# MCU.net
KiCad netlist of a schematic drawn in Altium Designer
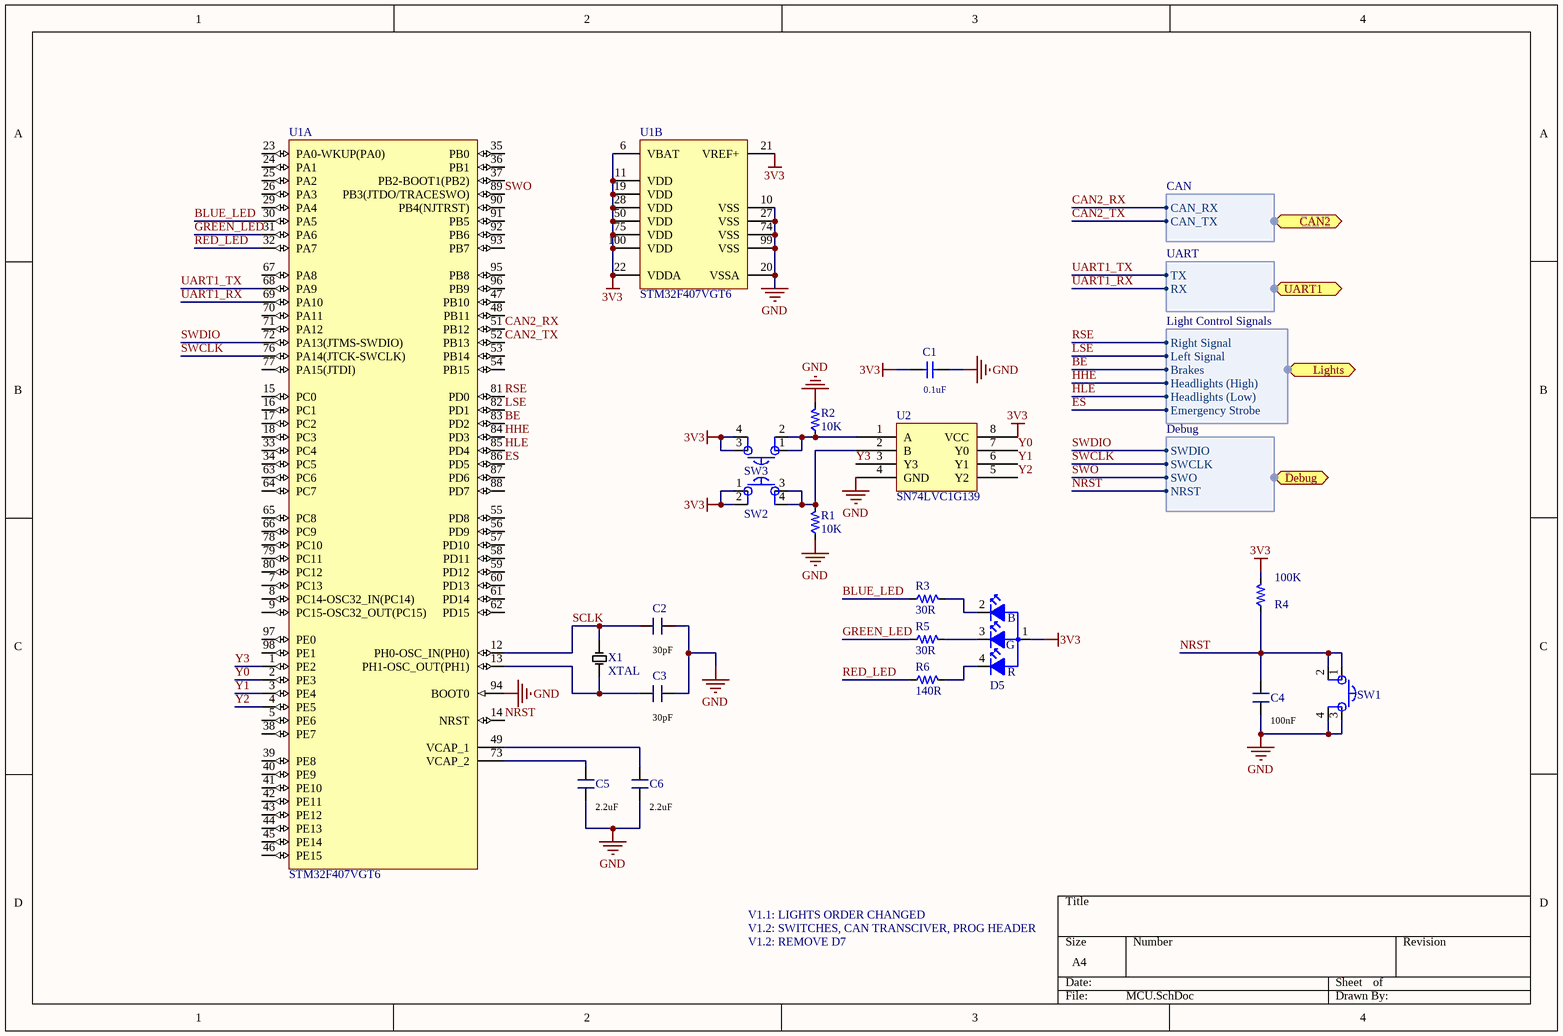
[diagram p0: MCU.SchDoc]

(export (version "E")
  (design (tool "Eeschema 10.0.6"))
  (components
    (comp (ref "C1")
      (value "SCH_GENERIC_CAPACITOR_0603")
      (footprint "PCB_GENERIC_SMD_0603")
      (description "Generic SMD capacitor 0603")
      (fields
        (field (name "TOLERANCE") "*%")
        (field (name "CAPACITANCE") "0.1uF")
        (field (name "VOLTAGE") "*V")
      )
      (libsource (lib "Generic 0603 Capacitor") (part "SCH_GENERIC_CAPACITOR_0603"))
    )
    (comp (ref "C2")
      (value "SCH_GENERIC_CAPACITOR_0603")
      (footprint "PCB_GENERIC_SMD_0603")
      (description "Generic SMD capacitor 0603")
      (fields (field (name "TOLERANCE") "*%") (field (name "CAPACITANCE") "30pF"))
      (libsource (lib "Capacitors") (part "SCH_GENERIC_CAPACITOR_0603"))
    )
    (comp (ref "C3")
      (value "SCH_GENERIC_CAPACITOR_0603")
      (footprint "PCB_GENERIC_SMD_0603")
      (description "Generic SMD capacitor 0603")
      (fields (field (name "TOLERANCE") "*%") (field (name "CAPACITANCE") "30pF"))
      (libsource (lib "Capacitors") (part "SCH_GENERIC_CAPACITOR_0603"))
    )
    (comp (ref "C4")
      (value "SCH_GENERIC_CAPACITOR_0603")
      (footprint "PCB_GENERIC_SMD_0603")
      (description "Generic SMD capacitor 0603")
      (fields (field (name "TOLERANCE") "*%") (field (name "CAPACITANCE") "100nF"))
      (libsource (lib "Capacitors") (part "SCH_GENERIC_CAPACITOR_0603"))
    )
    (comp (ref "C5")
      (value "SCH_GENERIC_CAPACITOR_0603")
      (footprint "PCB_GENERIC_SMD_0603")
      (description "Generic SMD capacitor 0603")
      (fields (field (name "TOLERANCE") "*%") (field (name "CAPACITANCE") "2.2uF"))
      (libsource (lib "Capacitors") (part "SCH_GENERIC_CAPACITOR_0603"))
    )
    (comp (ref "C6")
      (value "SCH_GENERIC_CAPACITOR_0603")
      (footprint "PCB_GENERIC_SMD_0603")
      (description "Generic SMD capacitor 0603")
      (fields (field (name "TOLERANCE") "*%") (field (name "CAPACITANCE") "2.2uF"))
      (libsource (lib "Capacitors") (part "SCH_GENERIC_CAPACITOR_0603"))
    )
    (comp (ref "D5")
      (value "D0S4-000CR-00")
      (footprint "CLMVB-FKA")
      (description "LED 4SMD RGB 2Vf 3Vf 3Vf 20mA 10mA 10mA")
      (libsource (lib "LED-4SMD") (part "D0S4-000CR-00"))
    )
    (comp (ref "R1")
      (value "SCH_GENERIC_RESISTOR_0603")
      (footprint "PCB_GENERIC_SMD_0603")
      (description "Generic SMD resistor 0603")
      (fields (field (name "RESISTANCE") "10K"))
      (libsource (lib "Generic 0603 Resistor") (part "SCH_GENERIC_RESISTOR_0603"))
    )
    (comp (ref "R2")
      (value "SCH_GENERIC_RESISTOR_0603")
      (footprint "PCB_GENERIC_SMD_0603")
      (description "Generic SMD resistor 0603")
      (fields (field (name "RESISTANCE") "10K"))
      (libsource (lib "Generic 0603 Resistor") (part "SCH_GENERIC_RESISTOR_0603"))
    )
    (comp (ref "R3")
      (value "SCH_GENERIC_RESISTOR_0603")
      (footprint "PCB_GENERIC_SMD_0603")
      (description "Generic SMD resistor 0603")
      (fields (field (name "RESISTANCE") "30R"))
      (libsource (lib "SCH_GENERIC_RESISTOR_0603") (part "SCH_GENERIC_RESISTOR_0603"))
    )
    (comp (ref "R4")
      (value "SCH_GENERIC_RESISTOR_0603")
      (footprint "PCB_GENERIC_SMD_0603")
      (description "Generic SMD resistor 0603")
      (fields (field (name "RESISTANCE") "100K"))
      (libsource (lib "Resistors") (part "SCH_GENERIC_RESISTOR_0603"))
    )
    (comp (ref "R5")
      (value "SCH_GENERIC_RESISTOR_0603")
      (footprint "PCB_GENERIC_SMD_0603")
      (description "Generic SMD resistor 0603")
      (fields (field (name "RESISTANCE") "30R"))
      (libsource (lib "SCH_GENERIC_RESISTOR_0603") (part "SCH_GENERIC_RESISTOR_0603"))
    )
    (comp (ref "R6")
      (value "SCH_GENERIC_RESISTOR_0603")
      (footprint "PCB_GENERIC_SMD_0603")
      (description "Generic SMD resistor 0603")
      (fields (field (name "RESISTANCE") "140R"))
      (libsource (lib "SCH_GENERIC_RESISTOR_0603") (part "SCH_GENERIC_RESISTOR_0603"))
    )
    (comp (ref "SW1")
      (value "Tactile Switch")
      (footprint "C&K 4 pin Tactile Switch")
      (libsource (lib "C&K 4 Pin Tactile Switch") (part "C&K Tactile Switch"))
    )
    (comp (ref "SW2")
      (value "Tactile Switch")
      (footprint "C&K 4 pin Tactile Switch")
      (libsource (lib "") (part "C&K Tactile Switch_1"))
    )
    (comp (ref "SW3")
      (value "Tactile Switch")
      (footprint "C&K 4 pin Tactile Switch")
      (libsource (lib "") (part "C&K Tactile Switch_1"))
    )
    (comp (ref "U1")
      (value "STM32F407VGT6")
      (footprint "STM-LQFP100_M")
      (fields (field (name "MANUFACTURER") "STMicroelectronics"))
      (libsource (lib "STMicroelectronics STM32 F4") (part "STM32F407VGT6"))
    )
    (comp (ref "U2")
      (value "SN74LVC1G139")
      (footprint "demux_24")
      (libsource (lib "demux") (part "demux_24"))
    )
    (comp (ref "X1") (value "XTAL") (footprint "CRYSTAL_8MHZ") (libsource (lib "Crystal") (part "Crystal")))
  )
  (nets
    (net (code "7") (name "/BE") (class "Default")
      (node (ref "U1") (pin "83") (pinfunction "PD2_83") (pintype "bidirectional"))
    )
    (net (code "8") (name "/BLUE_LED") (class "Default")
      (node (ref "R3") (pin "1") (pinfunction "1_1") (pintype "passive"))
      (node (ref "U1") (pin "30") (pinfunction "PA5_30") (pintype "bidirectional"))
    )
    (net (code "9") (name "/CAN2_RX") (class "Default")
      (node (ref "U1") (pin "51") (pinfunction "PB12_51") (pintype "bidirectional"))
    )
    (net (code "10") (name "/CAN2_TX") (class "Default")
      (node (ref "U1") (pin "52") (pinfunction "PB13_52") (pintype "bidirectional"))
    )
    (net (code "11") (name "/ES") (class "Default")
      (node (ref "U1") (pin "86") (pinfunction "PD5_86") (pintype "bidirectional"))
    )
    (net (code "12") (name "/GREEN_LED") (class "Default")
      (node (ref "R5") (pin "1") (pinfunction "1_1") (pintype "passive"))
      (node (ref "U1") (pin "31") (pinfunction "PA6_31") (pintype "bidirectional"))
    )
    (net (code "13") (name "/HHE") (class "Default")
      (node (ref "U1") (pin "84") (pinfunction "PD3_84") (pintype "bidirectional"))
    )
    (net (code "14") (name "/HLE") (class "Default")
      (node (ref "U1") (pin "85") (pinfunction "PD4_85") (pintype "bidirectional"))
    )
    (net (code "15") (name "/LSE") (class "Default")
      (node (ref "U1") (pin "82") (pinfunction "PD1_82") (pintype "bidirectional"))
    )
    (net (code "16") (name "/NRST") (class "Default")
      (node (ref "C4") (pin "1") (pinfunction "1_1") (pintype "passive"))
      (node (ref "R4") (pin "1") (pinfunction "1_1") (pintype "passive"))
      (node (ref "SW1") (pin "1") (pinfunction "1_1") (pintype "passive"))
      (node (ref "SW1") (pin "2") (pinfunction "2_2") (pintype "passive"))
      (node (ref "U1") (pin "14") (pinfunction "NRST_14") (pintype "bidirectional"))
    )
    (net (code "17") (name "/RED_LED") (class "Default")
      (node (ref "R6") (pin "1") (pinfunction "1_1") (pintype "passive"))
      (node (ref "U1") (pin "32") (pinfunction "PA7_32") (pintype "bidirectional"))
    )
    (net (code "18") (name "/RSE") (class "Default")
      (node (ref "U1") (pin "81") (pinfunction "PD0_81") (pintype "bidirectional"))
    )
    (net (code "19") (name "/SCLK") (class "Default")
      (node (ref "C2") (pin "2") (pinfunction "2_2") (pintype "passive"))
      (node (ref "U1") (pin "12") (pinfunction "PH0-OSC_IN(PH0)_12") (pintype "bidirectional"))
      (node (ref "X1") (pin "1") (pintype "passive"))
    )
    (net (code "20") (name "/SWCLK") (class "Default")
      (node (ref "U1") (pin "76") (pinfunction "PA14(JTCK-SWCLK)_76") (pintype "bidirectional"))
    )
    (net (code "21") (name "/SWDIO") (class "Default")
      (node (ref "U1") (pin "72") (pinfunction "PA13(JTMS-SWDIO)_72") (pintype "bidirectional"))
    )
    (net (code "22") (name "/SWO") (class "Default")
      (node (ref "U1") (pin "89") (pinfunction "PB3(JTDO/TRACESWO)_89") (pintype "bidirectional"))
    )
    (net (code "23") (name "/UART1_RX") (class "Default")
      (node (ref "U1") (pin "69") (pinfunction "PA10_69") (pintype "bidirectional"))
    )
    (net (code "24") (name "/UART1_TX") (class "Default")
      (node (ref "U1") (pin "68") (pinfunction "PA9_68") (pintype "bidirectional"))
    )
    (net (code "25") (name "/Y0") (class "Default")
      (node (ref "U1") (pin "2") (pinfunction "PE3_2") (pintype "bidirectional"))
      (node (ref "U2") (pin "7") (pinfunction "Y0_7") (pintype "passive"))
    )
    (net (code "26") (name "/Y1") (class "Default")
      (node (ref "U1") (pin "3") (pinfunction "PE4_3") (pintype "bidirectional"))
      (node (ref "U2") (pin "6") (pinfunction "Y1_6") (pintype "passive"))
    )
    (net (code "27") (name "/Y2") (class "Default")
      (node (ref "U1") (pin "4") (pinfunction "PE5_4") (pintype "bidirectional"))
      (node (ref "U2") (pin "5") (pinfunction "Y2_5") (pintype "passive"))
    )
    (net (code "28") (name "/Y3") (class "Default")
      (node (ref "U1") (pin "1") (pinfunction "PE2_1") (pintype "bidirectional"))
      (node (ref "U2") (pin "3") (pinfunction "Y3_3") (pintype "passive"))
    )
    (net (code "33") (name "3V3") (class "Default")
      (node (ref "C1") (pin "1") (pinfunction "1_1") (pintype "passive"))
      (node (ref "D5") (pin "1") (pinfunction "Red_1") (pintype "passive"))
      (node (ref "R4") (pin "2") (pinfunction "2_2") (pintype "passive"))
      (node (ref "SW2") (pin "1") (pinfunction "1_1") (pintype "passive"))
      (node (ref "SW2") (pin "2") (pinfunction "2_2") (pintype "passive"))
      (node (ref "SW3") (pin "3") (pinfunction "3_3") (pintype "passive"))
      (node (ref "SW3") (pin "4") (pinfunction "4_4") (pintype "passive"))
      (node (ref "U1") (pin "100") (pinfunction "VDD_100") (pintype "power_in"))
      (node (ref "U1") (pin "11") (pinfunction "VDD_11") (pintype "power_in"))
      (node (ref "U1") (pin "19") (pinfunction "VDD_19") (pintype "power_in"))
      (node (ref "U1") (pin "21") (pinfunction "VREF+_21") (pintype "power_in"))
      (node (ref "U1") (pin "22") (pinfunction "VDDA_22") (pintype "power_in"))
      (node (ref "U1") (pin "28") (pinfunction "VDD_28") (pintype "power_in"))
      (node (ref "U1") (pin "50") (pinfunction "VDD_50") (pintype "power_in"))
      (node (ref "U1") (pin "6") (pinfunction "VBAT_6") (pintype "power_in"))
      (node (ref "U1") (pin "75") (pinfunction "VDD_75") (pintype "power_in"))
      (node (ref "U2") (pin "8") (pinfunction "VCC_8") (pintype "passive"))
    )
    (net (code "34") (name "GND") (class "Default")
      (node (ref "C1") (pin "2") (pinfunction "2_2") (pintype "passive"))
      (node (ref "C2") (pin "1") (pinfunction "1_1") (pintype "passive"))
      (node (ref "C3") (pin "1") (pinfunction "1_1") (pintype "passive"))
      (node (ref "C4") (pin "2") (pinfunction "2_2") (pintype "passive"))
      (node (ref "C5") (pin "1") (pinfunction "1_1") (pintype "passive"))
      (node (ref "C6") (pin "1") (pinfunction "1_1") (pintype "passive"))
      (node (ref "R1") (pin "1") (pinfunction "1_1") (pintype "passive"))
      (node (ref "R2") (pin "2") (pinfunction "2_2") (pintype "passive"))
      (node (ref "SW1") (pin "3") (pinfunction "3_3") (pintype "passive"))
      (node (ref "SW1") (pin "4") (pinfunction "4_4") (pintype "passive"))
      (node (ref "U1") (pin "10") (pinfunction "VSS_10") (pintype "power_in"))
      (node (ref "U1") (pin "20") (pinfunction "VSSA_20") (pintype "power_in"))
      (node (ref "U1") (pin "27") (pinfunction "VSS_27") (pintype "power_in"))
      (node (ref "U1") (pin "74") (pinfunction "VSS_74") (pintype "power_in"))
      (node (ref "U1") (pin "94") (pinfunction "BOOT0_94") (pintype "input"))
      (node (ref "U1") (pin "99") (pinfunction "VSS_99") (pintype "power_in"))
      (node (ref "U2") (pin "4") (pinfunction "GND_4") (pintype "passive"))
    )
    (net (code "35") (name "Net-(D5-Blue)") (class "Default")
      (node (ref "D5") (pin "3") (pinfunction "Blue_3") (pintype "passive"))
      (node (ref "R5") (pin "2") (pinfunction "2_2") (pintype "passive"))
    )
    (net (code "36") (name "Net-(D5-Green)") (class "Default")
      (node (ref "D5") (pin "2") (pinfunction "Green_2") (pintype "passive"))
      (node (ref "R3") (pin "2") (pinfunction "2_2") (pintype "passive"))
    )
    (net (code "37") (name "Net-(D5-Pad4)") (class "Default")
      (node (ref "D5") (pin "4") (pinfunction "4_4") (pintype "passive"))
      (node (ref "R6") (pin "2") (pinfunction "2_2") (pintype "passive"))
    )
    (net (code "38") (name "Net-(U1A-PH1-OSC_OUT(PH1))") (class "Default")
      (node (ref "C3") (pin "2") (pinfunction "2_2") (pintype "passive"))
      (node (ref "U1") (pin "13") (pinfunction "PH1-OSC_OUT(PH1)_13") (pintype "bidirectional"))
      (node (ref "X1") (pin "2") (pintype "passive"))
    )
    (net (code "39") (name "Net-(U1A-VCAP_1)") (class "Default")
      (node (ref "C6") (pin "2") (pinfunction "2_2") (pintype "passive"))
      (node (ref "U1") (pin "49") (pinfunction "VCAP_1_49") (pintype "power_in"))
    )
    (net (code "40") (name "Net-(U1A-VCAP_2)") (class "Default")
      (node (ref "C5") (pin "2") (pinfunction "2_2") (pintype "passive"))
      (node (ref "U1") (pin "73") (pinfunction "VCAP_2_73") (pintype "power_in"))
    )
    (net (code "41") (name "Net-(U2-A)") (class "Default")
      (node (ref "R2") (pin "1") (pinfunction "1_1") (pintype "passive"))
      (node (ref "SW3") (pin "1") (pinfunction "1_1") (pintype "passive"))
      (node (ref "SW3") (pin "2") (pinfunction "2_2") (pintype "passive"))
      (node (ref "U2") (pin "1") (pinfunction "A_1") (pintype "passive"))
    )
    (net (code "42") (name "Net-(U2-B)") (class "Default")
      (node (ref "R1") (pin "2") (pinfunction "2_2") (pintype "passive"))
      (node (ref "SW2") (pin "3") (pinfunction "3_3") (pintype "passive"))
      (node (ref "SW2") (pin "4") (pinfunction "4_4") (pintype "passive"))
      (node (ref "U2") (pin "2") (pinfunction "B_2") (pintype "passive"))
    )
    (net (code "43") (name "unconnected-(U1A-PA0-WKUP(PA0)-Pad23)") (class "Default")
      (node (ref "U1") (pin "23") (pinfunction "PA0-WKUP(PA0)_23") (pintype "bidirectional"))
    )
    (net (code "44") (name "unconnected-(U1A-PA1-Pad24)") (class "Default")
      (node (ref "U1") (pin "24") (pinfunction "PA1_24") (pintype "bidirectional"))
    )
    (net (code "45") (name "unconnected-(U1A-PA2-Pad25)") (class "Default")
      (node (ref "U1") (pin "25") (pinfunction "PA2_25") (pintype "bidirectional"))
    )
    (net (code "46") (name "unconnected-(U1A-PA3-Pad26)") (class "Default")
      (node (ref "U1") (pin "26") (pinfunction "PA3_26") (pintype "bidirectional"))
    )
    (net (code "47") (name "unconnected-(U1A-PA4-Pad29)") (class "Default")
      (node (ref "U1") (pin "29") (pinfunction "PA4_29") (pintype "bidirectional"))
    )
    (net (code "48") (name "unconnected-(U1A-PA8-Pad67)") (class "Default")
      (node (ref "U1") (pin "67") (pinfunction "PA8_67") (pintype "bidirectional"))
    )
    (net (code "49") (name "unconnected-(U1A-PA11-Pad70)") (class "Default")
      (node (ref "U1") (pin "70") (pinfunction "PA11_70") (pintype "bidirectional"))
    )
    (net (code "50") (name "unconnected-(U1A-PA12-Pad71)") (class "Default")
      (node (ref "U1") (pin "71") (pinfunction "PA12_71") (pintype "bidirectional"))
    )
    (net (code "51") (name "unconnected-(U1A-PA15(JTDI)-Pad77)") (class "Default")
      (node (ref "U1") (pin "77") (pinfunction "PA15(JTDI)_77") (pintype "bidirectional"))
    )
    (net (code "52") (name "unconnected-(U1A-PB0-Pad35)") (class "Default")
      (node (ref "U1") (pin "35") (pinfunction "PB0_35") (pintype "bidirectional"))
    )
    (net (code "53") (name "unconnected-(U1A-PB1-Pad36)") (class "Default")
      (node (ref "U1") (pin "36") (pinfunction "PB1_36") (pintype "bidirectional"))
    )
    (net (code "54") (name "unconnected-(U1A-PB2-BOOT1(PB2)-Pad37)") (class "Default")
      (node (ref "U1") (pin "37") (pinfunction "PB2-BOOT1(PB2)_37") (pintype "bidirectional"))
    )
    (net (code "55") (name "unconnected-(U1A-PB4(NJTRST)-Pad90)") (class "Default")
      (node (ref "U1") (pin "90") (pinfunction "PB4(NJTRST)_90") (pintype "bidirectional"))
    )
    (net (code "56") (name "unconnected-(U1A-PB5-Pad91)") (class "Default")
      (node (ref "U1") (pin "91") (pinfunction "PB5_91") (pintype "bidirectional"))
    )
    (net (code "57") (name "unconnected-(U1A-PB6-Pad92)") (class "Default")
      (node (ref "U1") (pin "92") (pinfunction "PB6_92") (pintype "bidirectional"))
    )
    (net (code "58") (name "unconnected-(U1A-PB7-Pad93)") (class "Default")
      (node (ref "U1") (pin "93") (pinfunction "PB7_93") (pintype "bidirectional"))
    )
    (net (code "59") (name "unconnected-(U1A-PB8-Pad95)") (class "Default")
      (node (ref "U1") (pin "95") (pinfunction "PB8_95") (pintype "bidirectional"))
    )
    (net (code "60") (name "unconnected-(U1A-PB9-Pad96)") (class "Default")
      (node (ref "U1") (pin "96") (pinfunction "PB9_96") (pintype "bidirectional"))
    )
    (net (code "61") (name "unconnected-(U1A-PB10-Pad47)") (class "Default")
      (node (ref "U1") (pin "47") (pinfunction "PB10_47") (pintype "bidirectional"))
    )
    (net (code "62") (name "unconnected-(U1A-PB11-Pad48)") (class "Default")
      (node (ref "U1") (pin "48") (pinfunction "PB11_48") (pintype "bidirectional"))
    )
    (net (code "63") (name "unconnected-(U1A-PB14-Pad53)") (class "Default")
      (node (ref "U1") (pin "53") (pinfunction "PB14_53") (pintype "bidirectional"))
    )
    (net (code "64") (name "unconnected-(U1A-PB15-Pad54)") (class "Default")
      (node (ref "U1") (pin "54") (pinfunction "PB15_54") (pintype "bidirectional"))
    )
    (net (code "65") (name "unconnected-(U1A-PC0-Pad15)") (class "Default")
      (node (ref "U1") (pin "15") (pinfunction "PC0_15") (pintype "bidirectional"))
    )
    (net (code "66") (name "unconnected-(U1A-PC1-Pad16)") (class "Default")
      (node (ref "U1") (pin "16") (pinfunction "PC1_16") (pintype "bidirectional"))
    )
    (net (code "67") (name "unconnected-(U1A-PC2-Pad17)") (class "Default")
      (node (ref "U1") (pin "17") (pinfunction "PC2_17") (pintype "bidirectional"))
    )
    (net (code "68") (name "unconnected-(U1A-PC3-Pad18)") (class "Default")
      (node (ref "U1") (pin "18") (pinfunction "PC3_18") (pintype "bidirectional"))
    )
    (net (code "69") (name "unconnected-(U1A-PC4-Pad33)") (class "Default")
      (node (ref "U1") (pin "33") (pinfunction "PC4_33") (pintype "bidirectional"))
    )
    (net (code "70") (name "unconnected-(U1A-PC5-Pad34)") (class "Default")
      (node (ref "U1") (pin "34") (pinfunction "PC5_34") (pintype "bidirectional"))
    )
    (net (code "71") (name "unconnected-(U1A-PC6-Pad63)") (class "Default")
      (node (ref "U1") (pin "63") (pinfunction "PC6_63") (pintype "bidirectional"))
    )
    (net (code "72") (name "unconnected-(U1A-PC7-Pad64)") (class "Default")
      (node (ref "U1") (pin "64") (pinfunction "PC7_64") (pintype "bidirectional"))
    )
    (net (code "73") (name "unconnected-(U1A-PC8-Pad65)") (class "Default")
      (node (ref "U1") (pin "65") (pinfunction "PC8_65") (pintype "bidirectional"))
    )
    (net (code "74") (name "unconnected-(U1A-PC9-Pad66)") (class "Default")
      (node (ref "U1") (pin "66") (pinfunction "PC9_66") (pintype "bidirectional"))
    )
    (net (code "75") (name "unconnected-(U1A-PC10-Pad78)") (class "Default")
      (node (ref "U1") (pin "78") (pinfunction "PC10_78") (pintype "bidirectional"))
    )
    (net (code "76") (name "unconnected-(U1A-PC11-Pad79)") (class "Default")
      (node (ref "U1") (pin "79") (pinfunction "PC11_79") (pintype "bidirectional"))
    )
    (net (code "77") (name "unconnected-(U1A-PC12-Pad80)") (class "Default")
      (node (ref "U1") (pin "80") (pinfunction "PC12_80") (pintype "bidirectional"))
    )
    (net (code "78") (name "unconnected-(U1A-PC13-Pad7)") (class "Default")
      (node (ref "U1") (pin "7") (pinfunction "PC13_7") (pintype "bidirectional"))
    )
    (net (code "79") (name "unconnected-(U1A-PC14-OSC32_IN(PC14)-Pad8)") (class "Default")
      (node (ref "U1") (pin "8") (pinfunction "PC14-OSC32_IN(PC14)_8") (pintype "bidirectional"))
    )
    (net (code "80") (name "unconnected-(U1A-PC15-OSC32_OUT(PC15)-Pad9)") (class "Default")
      (node (ref "U1") (pin "9") (pinfunction "PC15-OSC32_OUT(PC15)_9") (pintype "bidirectional"))
    )
    (net (code "81") (name "unconnected-(U1A-PD6-Pad87)") (class "Default")
      (node (ref "U1") (pin "87") (pinfunction "PD6_87") (pintype "bidirectional"))
    )
    (net (code "82") (name "unconnected-(U1A-PD7-Pad88)") (class "Default")
      (node (ref "U1") (pin "88") (pinfunction "PD7_88") (pintype "bidirectional"))
    )
    (net (code "83") (name "unconnected-(U1A-PD8-Pad55)") (class "Default")
      (node (ref "U1") (pin "55") (pinfunction "PD8_55") (pintype "bidirectional"))
    )
    (net (code "84") (name "unconnected-(U1A-PD9-Pad56)") (class "Default")
      (node (ref "U1") (pin "56") (pinfunction "PD9_56") (pintype "bidirectional"))
    )
    (net (code "85") (name "unconnected-(U1A-PD10-Pad57)") (class "Default")
      (node (ref "U1") (pin "57") (pinfunction "PD10_57") (pintype "bidirectional"))
    )
    (net (code "86") (name "unconnected-(U1A-PD11-Pad58)") (class "Default")
      (node (ref "U1") (pin "58") (pinfunction "PD11_58") (pintype "bidirectional"))
    )
    (net (code "87") (name "unconnected-(U1A-PD12-Pad59)") (class "Default")
      (node (ref "U1") (pin "59") (pinfunction "PD12_59") (pintype "bidirectional"))
    )
    (net (code "88") (name "unconnected-(U1A-PD13-Pad60)") (class "Default")
      (node (ref "U1") (pin "60") (pinfunction "PD13_60") (pintype "bidirectional"))
    )
    (net (code "89") (name "unconnected-(U1A-PD14-Pad61)") (class "Default")
      (node (ref "U1") (pin "61") (pinfunction "PD14_61") (pintype "bidirectional"))
    )
    (net (code "90") (name "unconnected-(U1A-PD15-Pad62)") (class "Default")
      (node (ref "U1") (pin "62") (pinfunction "PD15_62") (pintype "bidirectional"))
    )
    (net (code "91") (name "unconnected-(U1A-PE0-Pad97)") (class "Default")
      (node (ref "U1") (pin "97") (pinfunction "PE0_97") (pintype "bidirectional"))
    )
    (net (code "92") (name "unconnected-(U1A-PE1-Pad98)") (class "Default")
      (node (ref "U1") (pin "98") (pinfunction "PE1_98") (pintype "bidirectional"))
    )
    (net (code "93") (name "unconnected-(U1A-PE6-Pad5)") (class "Default")
      (node (ref "U1") (pin "5") (pinfunction "PE6_5") (pintype "bidirectional"))
    )
    (net (code "94") (name "unconnected-(U1A-PE7-Pad38)") (class "Default")
      (node (ref "U1") (pin "38") (pinfunction "PE7_38") (pintype "bidirectional"))
    )
    (net (code "95") (name "unconnected-(U1A-PE8-Pad39)") (class "Default")
      (node (ref "U1") (pin "39") (pinfunction "PE8_39") (pintype "bidirectional"))
    )
    (net (code "96") (name "unconnected-(U1A-PE9-Pad40)") (class "Default")
      (node (ref "U1") (pin "40") (pinfunction "PE9_40") (pintype "bidirectional"))
    )
    (net (code "97") (name "unconnected-(U1A-PE10-Pad41)") (class "Default")
      (node (ref "U1") (pin "41") (pinfunction "PE10_41") (pintype "bidirectional"))
    )
    (net (code "98") (name "unconnected-(U1A-PE11-Pad42)") (class "Default")
      (node (ref "U1") (pin "42") (pinfunction "PE11_42") (pintype "bidirectional"))
    )
    (net (code "99") (name "unconnected-(U1A-PE12-Pad43)") (class "Default")
      (node (ref "U1") (pin "43") (pinfunction "PE12_43") (pintype "bidirectional"))
    )
    (net (code "100") (name "unconnected-(U1A-PE13-Pad44)") (class "Default")
      (node (ref "U1") (pin "44") (pinfunction "PE13_44") (pintype "bidirectional"))
    )
    (net (code "101") (name "unconnected-(U1A-PE14-Pad45)") (class "Default")
      (node (ref "U1") (pin "45") (pinfunction "PE14_45") (pintype "bidirectional"))
    )
    (net (code "102") (name "unconnected-(U1A-PE15-Pad46)") (class "Default")
      (node (ref "U1") (pin "46") (pinfunction "PE15_46") (pintype "bidirectional"))
    )
  )
)
